# PowerSupply.net
KiCad netlist of a schematic drawn in Altium Designer
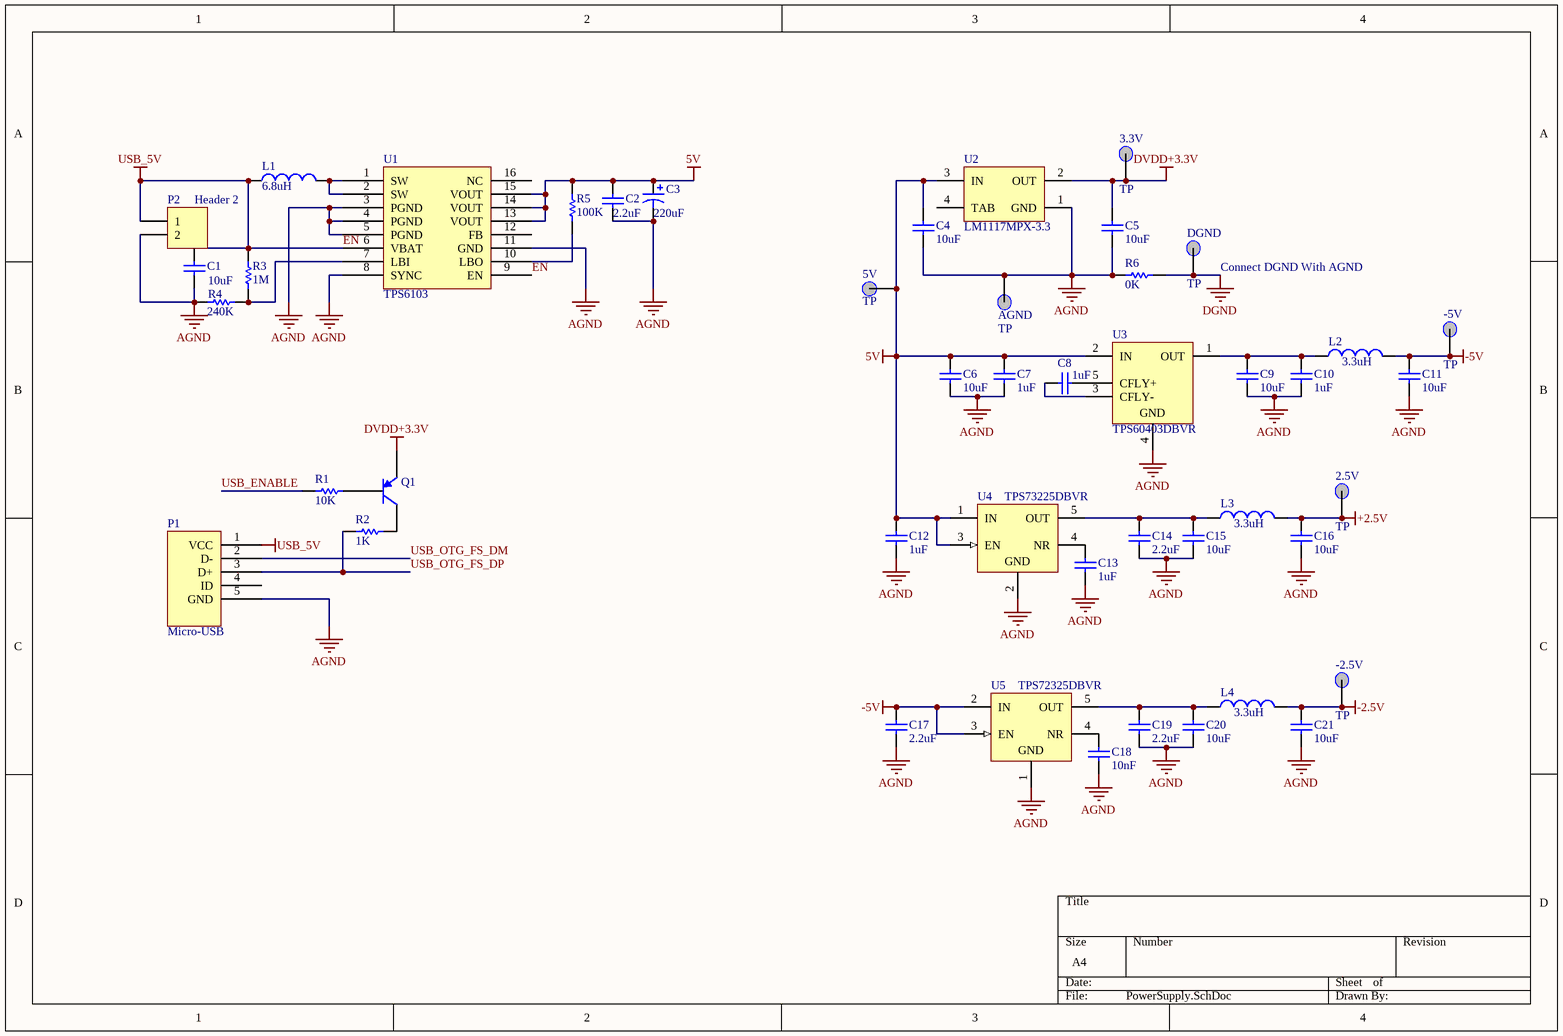
[diagram p0: PowerSupply.SchDoc]

(export (version "E")
  (design (tool "Eeschema 10.0.6"))
  (components
    (comp (ref "-2.5V") (value "TP") (footprint "TestPort") (libsource (lib "") (part "TestPoint_1")))
    (comp (ref "-5V") (value "TP") (footprint "TestPort") (libsource (lib "") (part "TestPoint_1")))
    (comp (ref "2.5V") (value "TP") (footprint "TestPort") (libsource (lib "") (part "TestPoint_1")))
    (comp (ref "3.3V") (value "TP") (footprint "TestPort") (libsource (lib "") (part "TestPoint_1")))
    (comp (ref "5V") (value "TP") (footprint "TestPort") (libsource (lib "CTs_FYF") (part "TestPoint")))
    (comp (ref "AGND") (value "TP") (footprint "TestPort") (libsource (lib "") (part "TestPoint_2")))
    (comp (ref "C1")
      (value "10uF")
      (footprint "1608[0603]")
      (description "Capacitor")
      (fields (field (name "PUBLISHER") "Altium Limited"))
      (libsource (lib "Miscellaneous Devices") (part "Cap"))
    )
    (comp (ref "C2")
      (value "2.2uF")
      (footprint "1608[0603]")
      (description "Capacitor")
      (fields (field (name "PUBLISHER") "Altium Limited"))
      (libsource (lib "Miscellaneous Devices") (part "Cap"))
    )
    (comp (ref "C3")
      (value "220uF")
      (footprint "6TPF220M5L")
      (description "Polarized Capacitor (Radial)")
      (fields (field (name "PUBLISHER") "Altium Limited"))
      (libsource (lib "Miscellaneous Devices") (part "Cap Pol1"))
    )
    (comp (ref "C4")
      (value "10uF")
      (footprint "1608[0603]")
      (description "Capacitor")
      (fields (field (name "PUBLISHER") "Altium Limited"))
      (libsource (lib "Miscellaneous Devices") (part "Cap"))
    )
    (comp (ref "C5")
      (value "10uF")
      (footprint "1608[0603]")
      (description "Capacitor")
      (fields (field (name "PUBLISHER") "Altium Limited"))
      (libsource (lib "Miscellaneous Devices") (part "Cap"))
    )
    (comp (ref "C6")
      (value "10uF")
      (footprint "1608[0603]")
      (description "Capacitor")
      (fields (field (name "PUBLISHER") "Altium Limited"))
      (libsource (lib "Miscellaneous Devices") (part "Cap"))
    )
    (comp (ref "C7")
      (value "1uF")
      (footprint "1608[0603]")
      (description "Capacitor")
      (fields (field (name "PUBLISHER") "Altium Limited"))
      (libsource (lib "Miscellaneous Devices") (part "Cap"))
    )
    (comp (ref "C8")
      (value "1uF")
      (footprint "1608[0603]")
      (description "Capacitor")
      (fields (field (name "PUBLISHER") "Altium Limited"))
      (libsource (lib "Miscellaneous Devices") (part "Cap"))
    )
    (comp (ref "C9")
      (value "10uF")
      (footprint "1608[0603]")
      (description "Capacitor")
      (fields (field (name "PUBLISHER") "Altium Limited"))
      (libsource (lib "Miscellaneous Devices") (part "Cap"))
    )
    (comp (ref "C10")
      (value "1uF")
      (footprint "1608[0603]")
      (description "Capacitor")
      (fields (field (name "PUBLISHER") "Altium Limited"))
      (libsource (lib "Miscellaneous Devices") (part "Cap"))
    )
    (comp (ref "C11")
      (value "10uF")
      (footprint "1608[0603]")
      (description "Capacitor")
      (fields (field (name "PUBLISHER") "Altium Limited"))
      (libsource (lib "Miscellaneous Devices") (part "Cap"))
    )
    (comp (ref "C12")
      (value "1uF")
      (footprint "1608[0603]")
      (description "Capacitor")
      (fields (field (name "PUBLISHER") "Altium Limited"))
      (libsource (lib "Miscellaneous Devices") (part "Cap"))
    )
    (comp (ref "C13")
      (value "1uF")
      (footprint "1608[0603]")
      (description "Capacitor")
      (fields (field (name "PUBLISHER") "Altium Limited"))
      (libsource (lib "Miscellaneous Devices") (part "Cap"))
    )
    (comp (ref "C14")
      (value "2.2uF")
      (footprint "1608[0603]")
      (description "Capacitor")
      (fields (field (name "PUBLISHER") "Altium Limited"))
      (libsource (lib "Miscellaneous Devices") (part "Cap"))
    )
    (comp (ref "C15")
      (value "10uF")
      (footprint "1608[0603]")
      (description "Capacitor")
      (fields (field (name "PUBLISHER") "Altium Limited"))
      (libsource (lib "Miscellaneous Devices") (part "Cap"))
    )
    (comp (ref "C16")
      (value "10uF")
      (footprint "1608[0603]")
      (description "Capacitor")
      (fields (field (name "PUBLISHER") "Altium Limited"))
      (libsource (lib "Miscellaneous Devices") (part "Cap"))
    )
    (comp (ref "C17")
      (value "2.2uF")
      (footprint "1608[0603]")
      (description "Capacitor")
      (fields (field (name "PUBLISHER") "Altium Limited"))
      (libsource (lib "Miscellaneous Devices") (part "Cap"))
    )
    (comp (ref "C18")
      (value "10nF")
      (footprint "1608[0603]")
      (description "Capacitor")
      (fields (field (name "PUBLISHER") "Altium Limited"))
      (libsource (lib "Miscellaneous Devices") (part "Cap"))
    )
    (comp (ref "C19")
      (value "2.2uF")
      (footprint "1608[0603]")
      (description "Capacitor")
      (fields (field (name "PUBLISHER") "Altium Limited"))
      (libsource (lib "Miscellaneous Devices") (part "Cap"))
    )
    (comp (ref "C20")
      (value "10uF")
      (footprint "1608[0603]")
      (description "Capacitor")
      (fields (field (name "PUBLISHER") "Altium Limited"))
      (libsource (lib "Miscellaneous Devices") (part "Cap"))
    )
    (comp (ref "C21")
      (value "10uF")
      (footprint "1608[0603]")
      (description "Capacitor")
      (fields (field (name "PUBLISHER") "Altium Limited"))
      (libsource (lib "Miscellaneous Devices") (part "Cap"))
    )
    (comp (ref "DGND") (value "TP") (footprint "TestPort") (libsource (lib "") (part "TestPoint_1")))
    (comp (ref "L1")
      (value "6.8uH")
      (footprint "B82464G4682M")
      (description "Inductor")
      (fields (field (name "PUBLISHER") "Altium Limited"))
      (libsource (lib "Miscellaneous Devices") (part "Inductor"))
    )
    (comp (ref "L2")
      (value "3.3uH")
      (footprint "2029")
      (description "Inductor")
      (fields (field (name "PUBLISHER") "Altium Limited"))
      (libsource (lib "Miscellaneous Devices") (part "Inductor"))
    )
    (comp (ref "L3")
      (value "3.3uH")
      (footprint "2029")
      (description "Inductor")
      (fields (field (name "PUBLISHER") "Altium Limited"))
      (libsource (lib "Miscellaneous Devices") (part "Inductor"))
    )
    (comp (ref "L4")
      (value "3.3uH")
      (footprint "2029")
      (description "Inductor")
      (fields (field (name "PUBLISHER") "Altium Limited"))
      (libsource (lib "Miscellaneous Devices") (part "Inductor"))
    )
    (comp (ref "P1")
      (value "Micro-USB")
      (footprint "Micro-USB")
      (libsource (lib "CTs_FYF") (part "Micro-USB"))
    )
    (comp (ref "P2")
      (value "Header 2")
      (footprint "HDR1X2")
      (description "Header, 2-Pin")
      (fields (field (name "PUBLISHER") "Altium Limited"))
      (libsource (lib "Miscellaneous Connectors") (part "Header 2"))
    )
    (comp (ref "Q1")
      (value "PNP")
      (footprint "SOT-23B_N")
      (description "PNP Bipolar Transistor")
      (fields (field (name "PUBLISHER") "Altium Limited"))
      (libsource (lib "Miscellaneous Devices") (part "PNP"))
    )
    (comp (ref "R1")
      (value "10K")
      (footprint "J1-0603")
      (description "Resistor")
      (fields (field (name "PUBLISHER") "Altium Limited"))
      (libsource (lib "Miscellaneous Devices") (part "Res1"))
    )
    (comp (ref "R2")
      (value "1K")
      (footprint "J1-0603")
      (description "Resistor")
      (fields (field (name "PUBLISHER") "Altium Limited"))
      (libsource (lib "Miscellaneous Devices") (part "Res1"))
    )
    (comp (ref "R3")
      (value "1M")
      (footprint "J1-0603")
      (description "Resistor")
      (fields (field (name "PUBLISHER") "Altium Limited"))
      (libsource (lib "Miscellaneous Devices") (part "Res1"))
    )
    (comp (ref "R4")
      (value "240K")
      (footprint "J1-0603")
      (description "Resistor")
      (fields (field (name "PUBLISHER") "Altium Limited"))
      (libsource (lib "Miscellaneous Devices") (part "Res1"))
    )
    (comp (ref "R5")
      (value "100K")
      (footprint "J1-0603")
      (description "Resistor")
      (fields (field (name "PUBLISHER") "Altium Limited"))
      (libsource (lib "Miscellaneous Devices") (part "Res1"))
    )
    (comp (ref "R6")
      (value "0K")
      (footprint "J1-0603")
      (description "Resistor")
      (fields (field (name "PUBLISHER") "Altium Limited"))
      (libsource (lib "Miscellaneous Devices") (part "Res1"))
    )
    (comp (ref "U1") (value "TPS6103") (footprint "TI_PWP_G16") (libsource (lib "CTs_FYF") (part "TPS6103")))
    (comp (ref "U2")
      (value "LM1117MPX-3.3")
      (footprint "MP04A_N")
      (description "800mA Low-Dropout Linear Regulator, 4-pin SOT-223")
      (fields
        (field (name "MANUFACTURER") "National Semiconductor")
        (field (name "PUBLISHER") "Altium Limited")
      )
      (libsource (lib "NSC LDO") (part "LM1117MPX-3.3"))
    )
    (comp (ref "U3")
      (value "TPS60403DBVR")
      (footprint "TI-DBV5_N")
      (fields (field (name "MANUFACTURER") "Texas Instruments"))
      (libsource (lib "TI Power Management Switching Regulator Charge Pump (Inductorless)") (part "TPS60403DBVR"))
    )
    (comp (ref "U4")
      (value "TPS73225DBVR")
      (footprint "TI-DBV5_N")
      (fields (field (name "MANUFACTURER") "Texas Instruments"))
      (libsource (lib "TI Power Management Linear Regulator Single Channel LDO (0-350mA)") (part "TPS73225DBVR"))
    )
    (comp (ref "U5")
      (value "TPS72325DBVR")
      (footprint "TI-DBV5_N")
      (fields (field (name "MANUFACTURER") "Texas Instruments"))
      (libsource (lib "TI Power Management Linear Regulator Single Channel LDO (0-350mA)") (part "TPS72325DBVR"))
    )
  )
  (nets
    (net (code "1") (name "+2.5V") (class "Default")
      (node (ref "2.5V") (pin "0") (pinfunction "0_0") (pintype "passive"))
      (node (ref "C16") (pin "2") (pinfunction "2_2") (pintype "passive"))
      (node (ref "L3") (pin "2") (pinfunction "2_2") (pintype "passive"))
    )
    (net (code "2") (name "-2.5V") (class "Default")
      (node (ref "-2.5V") (pin "0") (pinfunction "0_0") (pintype "passive"))
      (node (ref "C21") (pin "2") (pinfunction "2_2") (pintype "passive"))
      (node (ref "L4") (pin "2") (pinfunction "2_2") (pintype "passive"))
    )
    (net (code "3") (name "-5V") (class "Default")
      (node (ref "-5V") (pin "0") (pinfunction "0_0") (pintype "passive"))
      (node (ref "C11") (pin "2") (pinfunction "2_2") (pintype "passive"))
      (node (ref "C17") (pin "2") (pinfunction "2_2") (pintype "passive"))
      (node (ref "L2") (pin "2") (pinfunction "2_2") (pintype "passive"))
      (node (ref "U5") (pin "2") (pinfunction "IN_2") (pintype "power_in"))
      (node (ref "U5") (pin "3") (pinfunction "EN_3") (pintype "input"))
    )
    (net (code "4") (name "/USB_ENABLE") (class "Default")
      (node (ref "R1") (pin "1") (pinfunction "1_1") (pintype "passive"))
    )
    (net (code "5") (name "/USB_OTG_FS_DM") (class "Default")
      (node (ref "P1") (pin "2") (pinfunction "D-_2") (pintype "passive"))
    )
    (net (code "6") (name "/USB_OTG_FS_DP") (class "Default")
      (node (ref "P1") (pin "3") (pinfunction "D+_3") (pintype "passive"))
      (node (ref "R2") (pin "2") (pinfunction "2_2") (pintype "passive"))
    )
    (net (code "7") (name "5V") (class "Default")
      (node (ref "5V") (pin "0") (pinfunction "0_0") (pintype "passive"))
      (node (ref "C12") (pin "2") (pinfunction "2_2") (pintype "passive"))
      (node (ref "C2") (pin "2") (pinfunction "2_2") (pintype "passive"))
      (node (ref "C3") (pin "1") (pinfunction "1_1") (pintype "passive"))
      (node (ref "C4") (pin "1") (pinfunction "1_1") (pintype "passive"))
      (node (ref "C6") (pin "2") (pinfunction "2_2") (pintype "passive"))
      (node (ref "C7") (pin "2") (pinfunction "2_2") (pintype "passive"))
      (node (ref "R5") (pin "2") (pinfunction "2_2") (pintype "passive"))
      (node (ref "U1") (pin "13") (pinfunction "VOUT_13") (pintype "passive"))
      (node (ref "U1") (pin "14") (pinfunction "VOUT_14") (pintype "passive"))
      (node (ref "U1") (pin "15") (pinfunction "VOUT_15") (pintype "passive"))
      (node (ref "U2") (pin "3") (pinfunction "IN_3") (pintype "power_in"))
      (node (ref "U3") (pin "2") (pinfunction "IN_2") (pintype "power_in"))
      (node (ref "U4") (pin "1") (pinfunction "IN_1") (pintype "power_in"))
      (node (ref "U4") (pin "3") (pinfunction "EN_3") (pintype "input"))
    )
    (net (code "8") (name "AGND") (class "Default")
      (node (ref "AGND") (pin "0") (pinfunction "0_0") (pintype "passive"))
      (node (ref "C1") (pin "1") (pinfunction "1_1") (pintype "passive"))
      (node (ref "C10") (pin "1") (pinfunction "1_1") (pintype "passive"))
      (node (ref "C11") (pin "1") (pinfunction "1_1") (pintype "passive"))
      (node (ref "C12") (pin "1") (pinfunction "1_1") (pintype "passive"))
      (node (ref "C13") (pin "1") (pinfunction "1_1") (pintype "passive"))
      (node (ref "C14") (pin "1") (pinfunction "1_1") (pintype "passive"))
      (node (ref "C15") (pin "1") (pinfunction "1_1") (pintype "passive"))
      (node (ref "C16") (pin "1") (pinfunction "1_1") (pintype "passive"))
      (node (ref "C17") (pin "1") (pinfunction "1_1") (pintype "passive"))
      (node (ref "C18") (pin "1") (pinfunction "1_1") (pintype "passive"))
      (node (ref "C19") (pin "1") (pinfunction "1_1") (pintype "passive"))
      (node (ref "C2") (pin "1") (pinfunction "1_1") (pintype "passive"))
      (node (ref "C20") (pin "1") (pinfunction "1_1") (pintype "passive"))
      (node (ref "C21") (pin "1") (pinfunction "1_1") (pintype "passive"))
      (node (ref "C3") (pin "2") (pinfunction "2_2") (pintype "passive"))
      (node (ref "C4") (pin "2") (pinfunction "2_2") (pintype "passive"))
      (node (ref "C5") (pin "2") (pinfunction "2_2") (pintype "passive"))
      (node (ref "C6") (pin "1") (pinfunction "1_1") (pintype "passive"))
      (node (ref "C7") (pin "1") (pinfunction "1_1") (pintype "passive"))
      (node (ref "C9") (pin "1") (pinfunction "1_1") (pintype "passive"))
      (node (ref "P1") (pin "5") (pinfunction "GND_5") (pintype "passive"))
      (node (ref "P2") (pin "2") (pinfunction "2_2") (pintype "passive"))
      (node (ref "R4") (pin "1") (pinfunction "1_1") (pintype "passive"))
      (node (ref "R6") (pin "1") (pinfunction "1_1") (pintype "passive"))
      (node (ref "U1") (pin "11") (pinfunction "GND_11") (pintype "passive"))
      (node (ref "U1") (pin "3") (pinfunction "PGND_3") (pintype "passive"))
      (node (ref "U1") (pin "4") (pinfunction "PGND_4") (pintype "passive"))
      (node (ref "U1") (pin "5") (pinfunction "PGND_5") (pintype "passive"))
      (node (ref "U1") (pin "8") (pinfunction "SYNC_8") (pintype "passive"))
      (node (ref "U2") (pin "1") (pinfunction "GND_1") (pintype "power_in"))
      (node (ref "U3") (pin "4") (pinfunction "GND_4") (pintype "power_in"))
      (node (ref "U4") (pin "2") (pinfunction "GND_2") (pintype "power_in"))
      (node (ref "U5") (pin "1") (pinfunction "GND_1") (pintype "power_in"))
    )
    (net (code "9") (name "DGND") (class "Default")
      (node (ref "DGND") (pin "0") (pinfunction "0_0") (pintype "passive"))
      (node (ref "R6") (pin "2") (pinfunction "2_2") (pintype "passive"))
    )
    (net (code "10") (name "DVDD+3.3V") (class "Default")
      (node (ref "3.3V") (pin "0") (pinfunction "0_0") (pintype "passive"))
      (node (ref "C5") (pin "1") (pinfunction "1_1") (pintype "passive"))
      (node (ref "Q1") (pin "3") (pinfunction "E_3") (pintype "passive"))
      (node (ref "U2") (pin "2") (pinfunction "OUT_2") (pintype "power_in"))
    )
    (net (code "11") (name "Net-(L1-Pad2)") (class "Default")
      (node (ref "L1") (pin "2") (pinfunction "2_2") (pintype "passive"))
      (node (ref "U1") (pin "1") (pinfunction "SW_1") (pintype "passive"))
      (node (ref "U1") (pin "2") (pinfunction "SW_2") (pintype "passive"))
    )
    (net (code "12") (name "Net-(Q1-B)") (class "Default")
      (node (ref "Q1") (pin "2") (pinfunction "B_2") (pintype "passive"))
      (node (ref "R1") (pin "2") (pinfunction "2_2") (pintype "passive"))
    )
    (net (code "13") (name "Net-(Q1-C)") (class "Default")
      (node (ref "Q1") (pin "1") (pinfunction "C_1") (pintype "passive"))
      (node (ref "R2") (pin "1") (pinfunction "1_1") (pintype "passive"))
    )
    (net (code "14") (name "Net-(U1-LBI)") (class "Default")
      (node (ref "R3") (pin "1") (pinfunction "1_1") (pintype "passive"))
      (node (ref "R4") (pin "2") (pinfunction "2_2") (pintype "passive"))
      (node (ref "U1") (pin "7") (pinfunction "LBI_7") (pintype "passive"))
    )
    (net (code "15") (name "Net-(U1-LBO)") (class "Default")
      (node (ref "R5") (pin "1") (pinfunction "1_1") (pintype "passive"))
      (node (ref "U1") (pin "10") (pinfunction "LBO_10") (pintype "passive"))
    )
    (net (code "16") (name "Net-(U3-CFLY+)") (class "Default")
      (node (ref "C8") (pin "2") (pinfunction "2_2") (pintype "passive"))
      (node (ref "U3") (pin "5") (pinfunction "CFLY+_5") (pintype "passive"))
    )
    (net (code "17") (name "Net-(U3-CFLY-)") (class "Default")
      (node (ref "C8") (pin "1") (pinfunction "1_1") (pintype "passive"))
      (node (ref "U3") (pin "3") (pinfunction "CFLY-_3") (pintype "passive"))
    )
    (net (code "18") (name "Net-(U3-OUT)") (class "Default")
      (node (ref "C10") (pin "2") (pinfunction "2_2") (pintype "passive"))
      (node (ref "C9") (pin "2") (pinfunction "2_2") (pintype "passive"))
      (node (ref "L2") (pin "1") (pinfunction "1_1") (pintype "passive"))
      (node (ref "U3") (pin "1") (pinfunction "OUT_1") (pintype "power_in"))
    )
    (net (code "19") (name "Net-(U4-NR)") (class "Default")
      (node (ref "C13") (pin "2") (pinfunction "2_2") (pintype "passive"))
      (node (ref "U4") (pin "4") (pinfunction "NR_4") (pintype "passive"))
    )
    (net (code "20") (name "Net-(U4-OUT)") (class "Default")
      (node (ref "C14") (pin "2") (pinfunction "2_2") (pintype "passive"))
      (node (ref "C15") (pin "2") (pinfunction "2_2") (pintype "passive"))
      (node (ref "L3") (pin "1") (pinfunction "1_1") (pintype "passive"))
      (node (ref "U4") (pin "5") (pinfunction "OUT_5") (pintype "power_in"))
    )
    (net (code "21") (name "Net-(U5-NR)") (class "Default")
      (node (ref "C18") (pin "2") (pinfunction "2_2") (pintype "passive"))
      (node (ref "U5") (pin "4") (pinfunction "NR_4") (pintype "passive"))
    )
    (net (code "22") (name "Net-(U5-OUT)") (class "Default")
      (node (ref "C19") (pin "2") (pinfunction "2_2") (pintype "passive"))
      (node (ref "C20") (pin "2") (pinfunction "2_2") (pintype "passive"))
      (node (ref "L4") (pin "1") (pinfunction "1_1") (pintype "passive"))
      (node (ref "U5") (pin "5") (pinfunction "OUT_5") (pintype "power_in"))
    )
    (net (code "23") (name "USB_5V") (class "Default")
      (node (ref "C1") (pin "2") (pinfunction "2_2") (pintype "passive"))
      (node (ref "L1") (pin "1") (pinfunction "1_1") (pintype "passive"))
      (node (ref "P1") (pin "1") (pinfunction "VCC_1") (pintype "passive"))
      (node (ref "P2") (pin "1") (pinfunction "1_1") (pintype "passive"))
      (node (ref "R3") (pin "2") (pinfunction "2_2") (pintype "passive"))
      (node (ref "U1") (pin "6") (pinfunction "VBAT_6") (pintype "passive"))
      (node (ref "U1") (pin "9") (pinfunction "EN_9") (pintype "passive"))
    )
    (net (code "24") (name "unconnected-(P1-ID-Pad4)") (class "Default")
      (node (ref "P1") (pin "4") (pinfunction "ID_4") (pintype "passive"))
    )
    (net (code "25") (name "unconnected-(U1-FB-Pad12)") (class "Default")
      (node (ref "U1") (pin "12") (pinfunction "FB_12") (pintype "passive"))
    )
    (net (code "26") (name "unconnected-(U1-NC-Pad16)") (class "Default")
      (node (ref "U1") (pin "16") (pinfunction "NC_16") (pintype "passive"))
    )
    (net (code "27") (name "unconnected-(U2-TAB-Pad4)") (class "Default")
      (node (ref "U2") (pin "4") (pinfunction "TAB_4") (pintype "power_in"))
    )
  )
)
